# Servo_Tester.net
KiCad netlist of a schematic drawn in Altium Designer
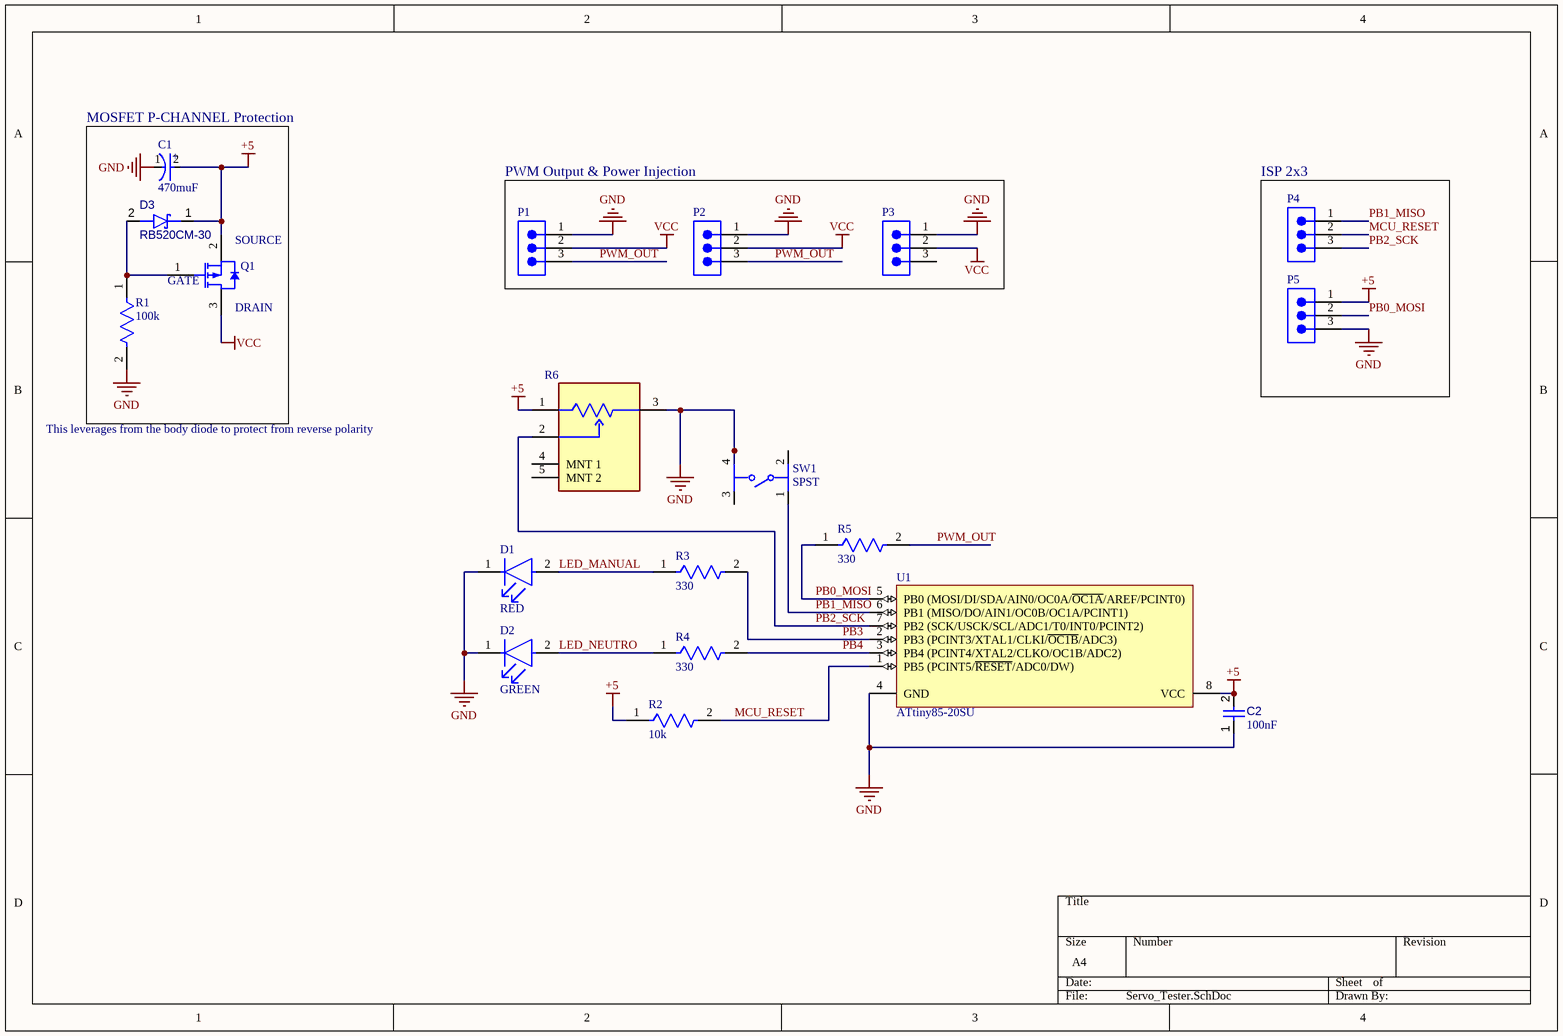
[diagram p0: Servo_Tester.SchDoc]

(export (version "E")
  (design (tool "Eeschema 10.0.6"))
  (components
    (comp (ref "C1")
      (value "470muF")
      (footprint "FP-RAD-TH-D_10_0_5-L_12_5-MFG")
      (description "Aluminum Electrolytic Capacitors (Radial Lead Type) 470uF ±20% 16V")
      (fields (field (name "TOLERANCE") "20%"))
      (libsource (lib "Altium Content Vault") (part "203bc49f2ac43e59fd269a8c329ed05"))
    )
    (comp (ref "C2")
      (value "100nF")
      (footprint "CAPC1608X90X40NL10T20")
      (description "Chip Capacitor, 100 nF, +/- 10%, 50 V, 0603 (1608 Metric)")
      (fields (field (name "TOLERANCE") "10%") (field (name "Comment") "Capacitor 100 nF +/-10% 50 V 0603"))
      (libsource (lib "EMEA - Instituto Superior Técnico - AeroTéc") (part "CAP-NP-2"))
    )
    (comp (ref "D1")
      (value "RED")
      (footprint "FP-LTST-C191KRKT-MFG")
      (fields (field (name "VOLTAGE") "2V"))
      (libsource (lib "Altium Content Vault") (part "8706943c75ba83719d021d2fdc84c58"))
    )
    (comp (ref "D2")
      (value "GREEN")
      (footprint "FP-LTST-C191KGKT-MFG")
      (libsource (lib "Altium Content Vault") (part "8706943c75ba83719d021d2fdc84c58"))
    )
    (comp (ref "D3")
      (value "RB520CM-30")
      (footprint "ROHM-VMN2-2_V")
      (description "DIODE SCHOTTKY 30V 100MA VMN2M")
      (libsource (lib "EMEA - Instituto Superior Técnico - AeroTéc") (part "D-SKY-KA2"))
    )
    (comp (ref "P1")
      (value "TSW-103-07-F-S")
      (footprint "SMTC-TSW-103-07-X-S")
      (description "0.025\" SQ Post Header, Through-hole, Vertical, -55 to 125 degC, 2.54 mm Pitch, 3-Pin, Male, RoHS")
      (fields (field (name "MANUFACTURER") "Samtec"))
      (libsource (lib "Altium Content Vault") (part "SMTC-TSW-103-X-X-S-X"))
    )
    (comp (ref "P2")
      (value "TSW-103-07-F-S")
      (footprint "SMTC-TSW-103-07-X-S")
      (description "0.025\" SQ Post Header, Through-hole, Vertical, -55 to 125 degC, 2.54 mm Pitch, 3-Pin, Male, RoHS")
      (fields (field (name "MANUFACTURER") "Samtec"))
      (libsource (lib "Altium Content Vault") (part "SMTC-TSW-103-X-X-S-X"))
    )
    (comp (ref "P3")
      (value "TSW-103-07-F-S")
      (footprint "SMTC-TSW-103-07-X-S")
      (description "0.025\" SQ Post Header, Through-hole, Vertical, -55 to 125 degC, 2.54 mm Pitch, 3-Pin, Male, RoHS")
      (fields (field (name "MANUFACTURER") "Samtec"))
      (libsource (lib "Altium Content Vault") (part "SMTC-TSW-103-X-X-S-X"))
    )
    (comp (ref "P4")
      (value "TSW-103-07-F-S")
      (footprint "SMTC-TSW-103-07-X-S")
      (description "0.025\" SQ Post Header, Through-hole, Vertical, -55 to 125 degC, 2.54 mm Pitch, 3-Pin, Male, RoHS")
      (fields (field (name "MANUFACTURER") "Samtec"))
      (libsource (lib "Altium Content Vault") (part "SMTC-TSW-103-X-X-S-X"))
    )
    (comp (ref "P5")
      (value "TSW-103-07-F-S")
      (footprint "SMTC-TSW-103-07-X-S")
      (description "0.025\" SQ Post Header, Through-hole, Vertical, -55 to 125 degC, 2.54 mm Pitch, 3-Pin, Male, RoHS")
      (fields (field (name "MANUFACTURER") "Samtec"))
      (libsource (lib "Altium Content Vault") (part "SMTC-TSW-103-X-X-S-X"))
    )
    (comp (ref "Q1")
      (value "AO3401A")
      (footprint "AO-SOT-23-3L_V")
      (description "P-Channel MOSFET, 30 V, 4 A, -55 to 150 degC, 3-Pin SOT-23-3L, RoHS, Tape and Reel")
      (fields (field (name "MANUFACTURER") "Alpha and Omega"))
      (libsource (lib "Altium Content Vault") (part "PEMOS-GSD-3"))
    )
    (comp (ref "R1")
      (value "100k")
      (footprint "FP-RC0603-0_55-MFG")
      (description "RES SMD 100K OHM 1% 1/10W 0603")
      (fields (field (name "TOLERANCE") "1%"))
      (libsource (lib "Altium Content Vault") (part "1029c3af85768c4190bb7ad29bc67b5"))
    )
    (comp (ref "R2")
      (value "10k")
      (footprint "FP-RC0603-0_55-IPC_C")
      (description "RES 10K OHM 1% 1/10W 0603")
      (fields (field (name "TOLERANCE") "1%"))
      (libsource (lib "Altium Content Vault") (part "1029c3af85768c4190bb7ad29bc67b5"))
    )
    (comp (ref "R3")
      (value "330")
      (footprint "FP-RK73H2A-IPC_B")
      (description "330Ω ±1% 0.25W Chip Resistor 0805 Thick Film AEC-Q200 Qualified")
      (fields (field (name "TOLERANCE") "1%"))
      (libsource (lib "Altium Content Vault") (part "1029c3af85768c4190bb7ad29bc67b5"))
    )
    (comp (ref "R4")
      (value "330")
      (footprint "FP-RK73H2A-IPC_B")
      (description "330Ω ±1% 0.25W Chip Resistor 0805 Thick Film AEC-Q200 Qualified")
      (fields (field (name "TOLERANCE") "1%"))
      (libsource (lib "Altium Content Vault") (part "1029c3af85768c4190bb7ad29bc67b5"))
    )
    (comp (ref "R5")
      (value "330")
      (footprint "FP-RK73H2A-IPC_B")
      (description "330Ω ±1% 0.25W Chip Resistor 0805 Thick Film AEC-Q200 Qualified")
      (fields (field (name "TOLERANCE") "1%"))
      (libsource (lib "Altium Content Vault") (part "1029c3af85768c4190bb7ad29bc67b5"))
    )
    (comp (ref "R6")
      (value "10k")
      (footprint "FP-RK09L1140A2U-MFG")
      (description "9mm Size Metal Shaft Snap-in Type RK09L Series")
      (fields
        (field (name "TOLERANCE") "20%")
        (field (name "OCTOPART") "https://octopart.com/rk09l1140a2u-alps-7850070")
      )
      (libsource (lib "Altium Content Vault") (part "0c568a6e0ac31b8b52ae5f6704acd43"))
    )
    (comp (ref "SW1")
      (value "SPST")
      (footprint "FP-1-1977223-9-MFG")
      (description "SWITCH TACTILE SPST-NO 0.05A 24V")
      (libsource (lib "Altium Content Vault") (part "b8895f3f4cefb76e1819d2863dba89b"))
    )
    (comp (ref "U1")
      (value "ATtiny85-20SU")
      (footprint "8S2_M")
      (libsource (lib "Altium Content Vault") (part "MC-8B-ATT25-IL8"))
    )
  )
  (nets
    (net (code "1") (name "+5") (class "Default")
      (node (ref "C1") (pin "2") (pinfunction "A_2") (pintype "passive"))
      (node (ref "C2") (pin "2") (pinfunction "2_2") (pintype "passive"))
      (node (ref "D3") (pin "1") (pinfunction "K_1") (pintype "passive"))
      (node (ref "P5") (pin "1") (pinfunction "1_1") (pintype "passive"))
      (node (ref "Q1") (pin "2") (pinfunction "SOURCE_2") (pintype "passive"))
      (node (ref "R2") (pin "1") (pinfunction "1_1") (pintype "passive"))
      (node (ref "R6") (pin "1") (pinfunction "1_1") (pintype "passive"))
      (node (ref "U1") (pin "8") (pinfunction "VCC_8") (pintype "power_in"))
    )
    (net (code "2") (name "/LED_MANUAL") (class "Default")
      (node (ref "D1") (pin "2") (pinfunction "A_2") (pintype "passive"))
      (node (ref "R3") (pin "1") (pinfunction "1_1") (pintype "passive"))
    )
    (net (code "3") (name "/LED_NEUTRO") (class "Default")
      (node (ref "D2") (pin "2") (pinfunction "A_2") (pintype "passive"))
      (node (ref "R4") (pin "1") (pinfunction "1_1") (pintype "passive"))
    )
    (net (code "4") (name "/MCU_RESET") (class "Default")
      (node (ref "P4") (pin "2") (pinfunction "2_2") (pintype "passive"))
      (node (ref "R2") (pin "2") (pinfunction "2_2") (pintype "passive"))
      (node (ref "U1") (pin "1") (pinfunction "PB5_(PCINT5/~{RESET}/ADC0/DW)_1") (pintype "bidirectional"))
    )
    (net (code "5") (name "/PB0_MOSI") (class "Default")
      (node (ref "P5") (pin "2") (pinfunction "2_2") (pintype "passive"))
      (node (ref "R5") (pin "1") (pinfunction "1_1") (pintype "passive"))
      (node (ref "U1") (pin "5") (pinfunction "PB0_(MOSI/DI/SDA/AIN0/OC0A/~{OC1A}/AREF/PCINT0)_5") (pintype "bidirectional"))
    )
    (net (code "6") (name "/PB1_MISO") (class "Default")
      (node (ref "P4") (pin "1") (pinfunction "1_1") (pintype "passive"))
      (node (ref "SW1") (pin "1") (pinfunction "1_1") (pintype "passive"))
      (node (ref "U1") (pin "6") (pinfunction "PB1_(MISO/DO/AIN1/OC0B/OC1A/PCINT1)_6") (pintype "bidirectional"))
    )
    (net (code "7") (name "/PB2_SCK") (class "Default")
      (node (ref "P4") (pin "3") (pinfunction "3_3") (pintype "passive"))
      (node (ref "R6") (pin "2") (pinfunction "2_2") (pintype "passive"))
      (node (ref "U1") (pin "7") (pinfunction "PB2_(SCK/USCK/SCL/ADC1/T0/INT0/PCINT2)_7") (pintype "bidirectional"))
    )
    (net (code "8") (name "/PB3") (class "Default")
      (node (ref "R3") (pin "2") (pinfunction "2_2") (pintype "passive"))
      (node (ref "U1") (pin "2") (pinfunction "PB3_(PCINT3/XTAL1/CLKI/~{OC1B}/ADC3)_2") (pintype "bidirectional"))
    )
    (net (code "9") (name "/PB4") (class "Default")
      (node (ref "R4") (pin "2") (pinfunction "2_2") (pintype "passive"))
      (node (ref "U1") (pin "3") (pinfunction "PB4_(PCINT4/XTAL2/CLKO/OC1B/ADC2)_3") (pintype "bidirectional"))
    )
    (net (code "10") (name "/PWM_OUT") (class "Default")
      (node (ref "P1") (pin "3") (pinfunction "3_3") (pintype "passive"))
      (node (ref "P2") (pin "3") (pinfunction "3_3") (pintype "passive"))
      (node (ref "R5") (pin "2") (pinfunction "2_2") (pintype "passive"))
    )
    (net (code "11") (name "GND") (class "Default")
      (node (ref "C1") (pin "1") (pinfunction "C_1") (pintype "passive"))
      (node (ref "C2") (pin "1") (pinfunction "1_1") (pintype "passive"))
      (node (ref "D1") (pin "1") (pinfunction "C_1") (pintype "passive"))
      (node (ref "D2") (pin "1") (pinfunction "C_1") (pintype "passive"))
      (node (ref "P1") (pin "1") (pinfunction "1_1") (pintype "passive"))
      (node (ref "P2") (pin "1") (pinfunction "1_1") (pintype "passive"))
      (node (ref "P3") (pin "1") (pinfunction "1_1") (pintype "passive"))
      (node (ref "P5") (pin "3") (pinfunction "3_3") (pintype "passive"))
      (node (ref "R1") (pin "2") (pinfunction "2_2") (pintype "passive"))
      (node (ref "R6") (pin "3") (pinfunction "3_3") (pintype "passive"))
      (node (ref "SW1") (pin "4") (pinfunction "4_4") (pintype "passive"))
      (node (ref "U1") (pin "4") (pinfunction "GND_4") (pintype "power_in"))
    )
    (net (code "12") (name "Net-(D3-A)") (class "Default")
      (node (ref "D3") (pin "2") (pinfunction "A_2") (pintype "passive"))
      (node (ref "Q1") (pin "1") (pinfunction "GATE_1") (pintype "passive"))
      (node (ref "R1") (pin "1") (pinfunction "1_1") (pintype "passive"))
    )
    (net (code "13") (name "VCC") (class "Default")
      (node (ref "P1") (pin "2") (pinfunction "2_2") (pintype "passive"))
      (node (ref "P2") (pin "2") (pinfunction "2_2") (pintype "passive"))
      (node (ref "P3") (pin "2") (pinfunction "2_2") (pintype "passive"))
      (node (ref "Q1") (pin "3") (pinfunction "DRAIN_3") (pintype "passive"))
    )
    (net (code "14") (name "unconnected-(P3-Pad3)") (class "Default")
      (node (ref "P3") (pin "3") (pinfunction "3_3") (pintype "passive"))
    )
    (net (code "15") (name "unconnected-(R6-MNT_1-Pad4)") (class "Default")
      (node (ref "R6") (pin "4") (pinfunction "MNT_1_4") (pintype "passive"))
    )
    (net (code "16") (name "unconnected-(R6-MNT_2-Pad5)") (class "Default")
      (node (ref "R6") (pin "5") (pinfunction "MNT_2_5") (pintype "passive"))
    )
    (net (code "17") (name "unconnected-(SW1-Pad2)") (class "Default")
      (node (ref "SW1") (pin "2") (pinfunction "2_2") (pintype "passive"))
    )
    (net (code "18") (name "unconnected-(SW1-Pad3)") (class "Default")
      (node (ref "SW1") (pin "3") (pinfunction "3_3") (pintype "passive"))
    )
  )
)
